# RasPi-BplusHAT.net
KiCad netlist of a schematic drawn in Altium Designer
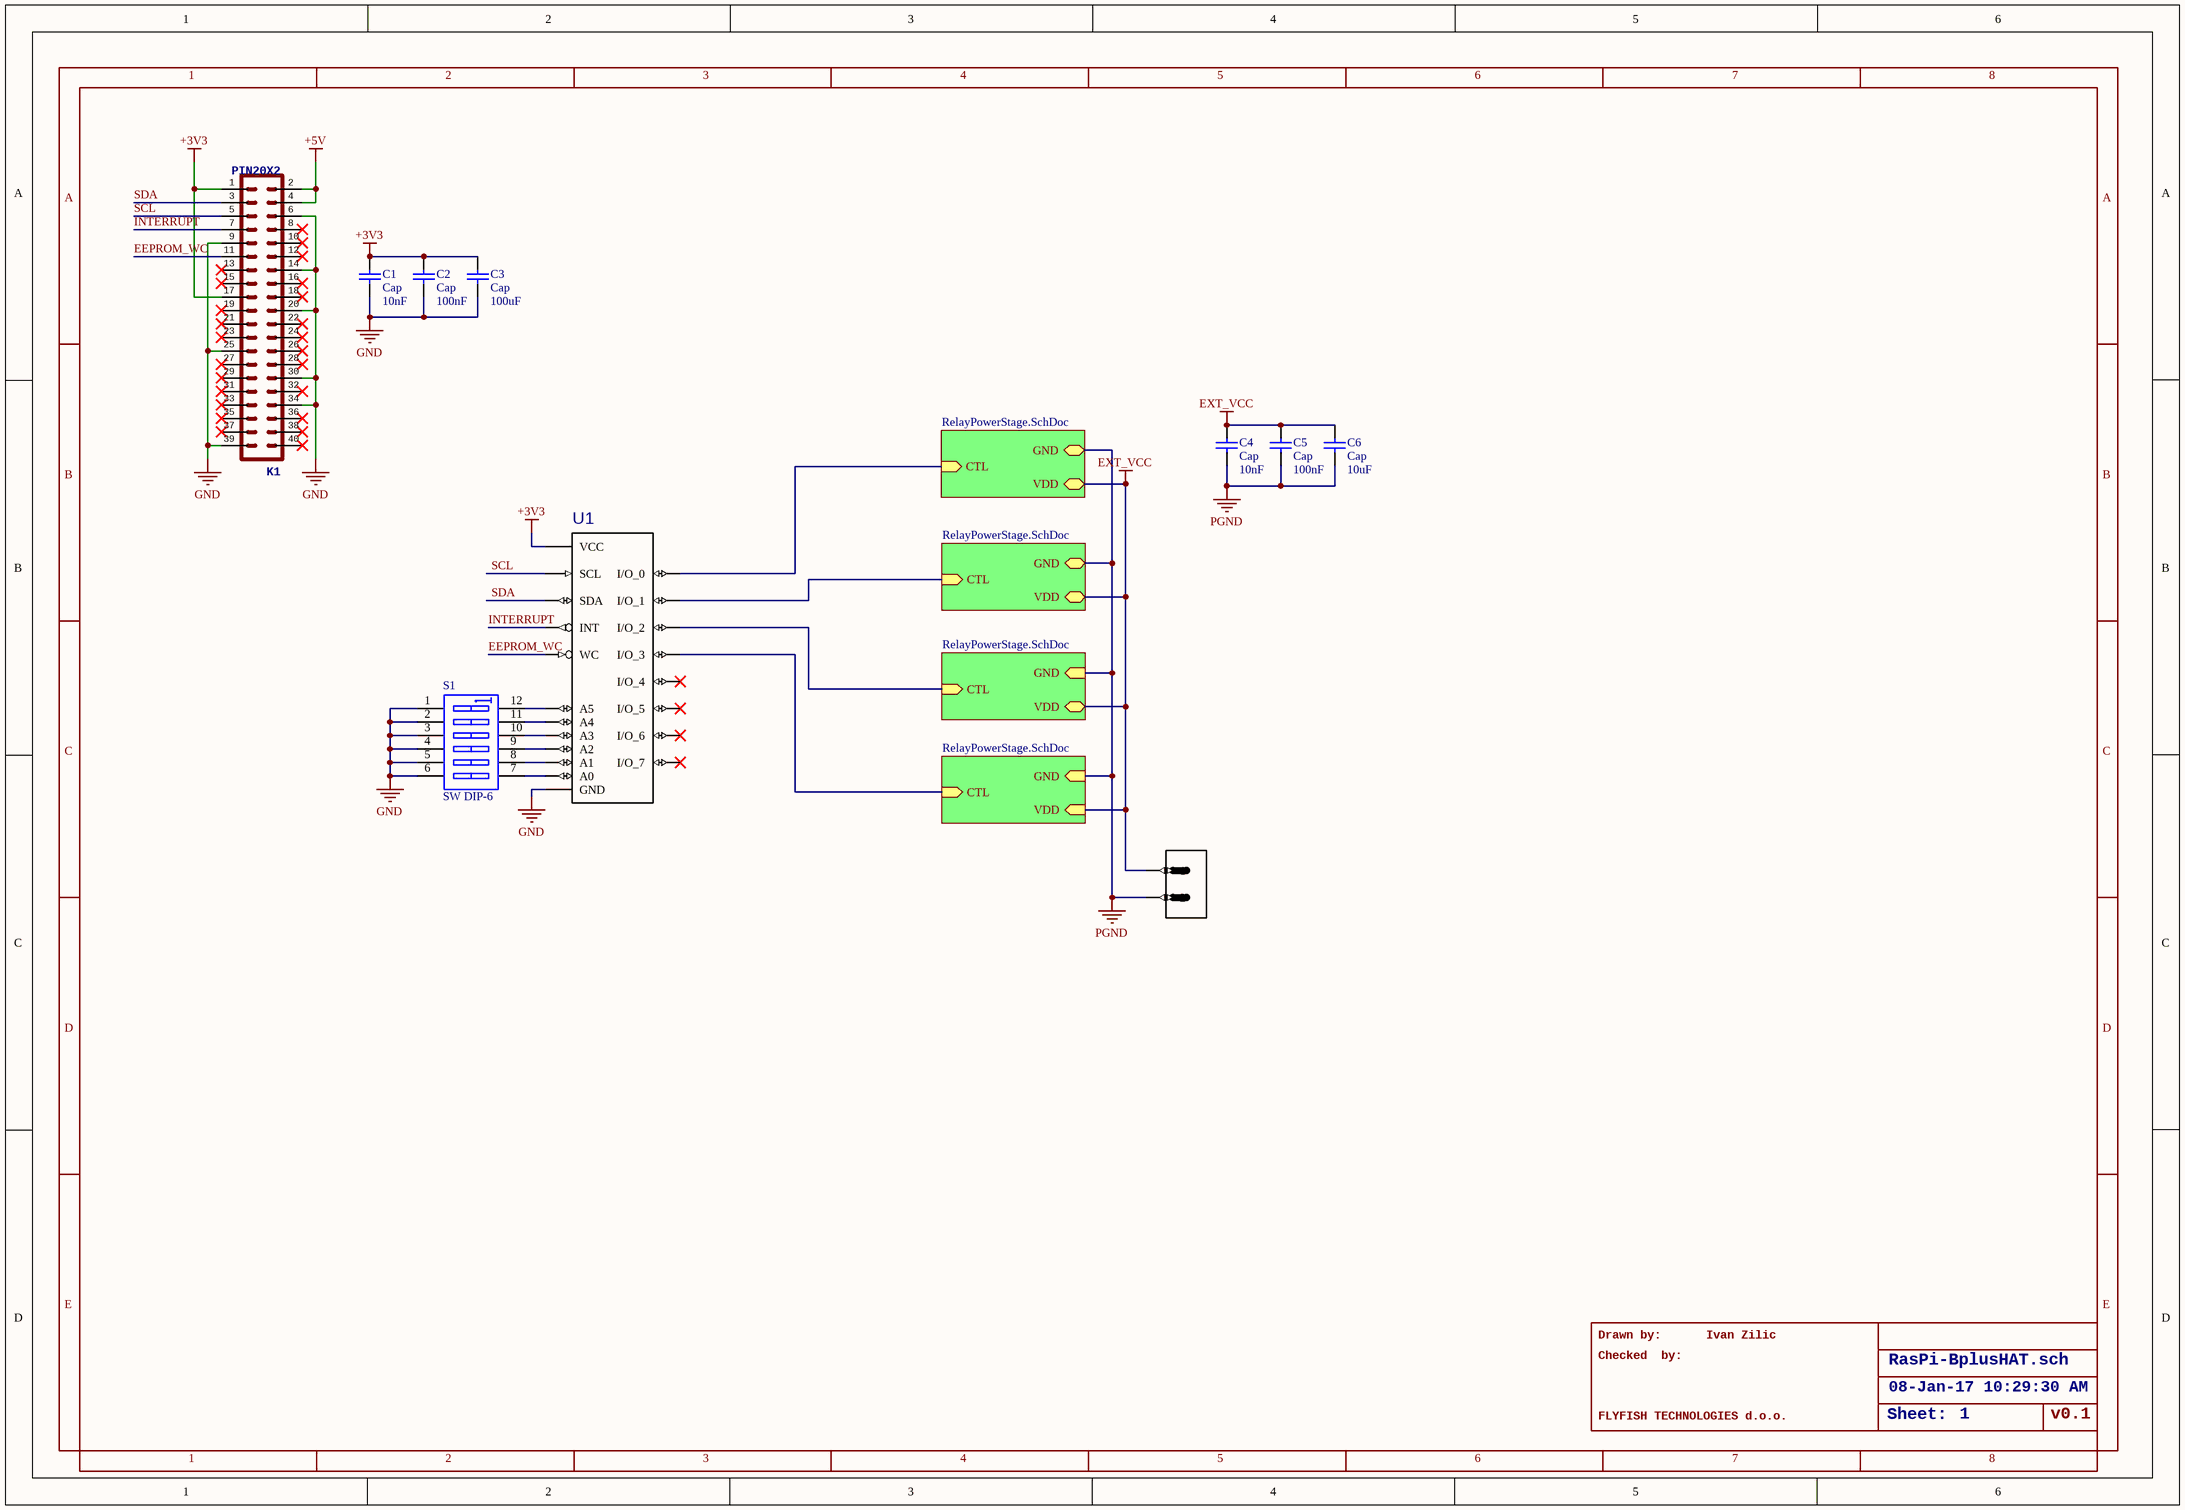
[diagram p0: RasPi-BplusHAT.SchDoc]

(export (version "E")
  (design (tool "Eeschema 10.0.6"))
  (components
    (comp (ref "C1")
      (value "Cap")
      (footprint "6-0805_N")
      (description "Capacitor")
      (fields (field (name "ALTIUM_VALUE") "10nF") (field (name "PUBLISHER") "Altium Limited"))
      (libsource (lib "Miscellaneous Devices") (part "Cap"))
    )
    (comp (ref "C2")
      (value "Cap")
      (footprint "6-0805_N")
      (description "Capacitor")
      (fields (field (name "ALTIUM_VALUE") "100nF") (field (name "PUBLISHER") "Altium Limited"))
      (libsource (lib "Miscellaneous Devices") (part "Cap"))
    )
    (comp (ref "C3")
      (value "Cap")
      (footprint "6-0805_N")
      (description "Capacitor")
      (fields (field (name "ALTIUM_VALUE") "100uF") (field (name "PUBLISHER") "Altium Limited"))
      (libsource (lib "Miscellaneous Devices") (part "Cap"))
    )
    (comp (ref "C4")
      (value "Cap")
      (footprint "6-0805_N")
      (description "Capacitor")
      (fields (field (name "ALTIUM_VALUE") "10nF") (field (name "PUBLISHER") "Altium Limited"))
      (libsource (lib "Miscellaneous Devices") (part "Cap"))
    )
    (comp (ref "C5")
      (value "Cap")
      (footprint "6-0805_N")
      (description "Capacitor")
      (fields (field (name "ALTIUM_VALUE") "100nF") (field (name "PUBLISHER") "Altium Limited"))
      (libsource (lib "Miscellaneous Devices") (part "Cap"))
    )
    (comp (ref "C6")
      (value "Cap")
      (footprint "C1210_N")
      (description "Capacitor")
      (fields (field (name "ALTIUM_VALUE") "10uF") (field (name "PUBLISHER") "Altium Limited"))
      (libsource (lib "Miscellaneous Devices") (part "Cap"))
    )
    (comp (ref "J1")
      (value "1760510000")
      (footprint "1760490000")
      (description "Conn Terminal Block 2 POS 5.08mm Solder ST Thru-Hole 16A")
      (fields (field (name "MF") "Weidmuller"))
      (libsource (lib "1760510000") (part "1760510000"))
    )
    (comp (ref "K1")
      (value "PIN20X2")
      (footprint "HDR2X20")
      (fields (field (name ">VALUE") "PIN20X2") (field (name ">NAME") "K1"))
      (libsource (lib "FLYFISH") (part "PIN20X2"))
    )
    (comp (ref "S1")
      (value "SW DIP-6")
      (footprint "DIP-12/SW")
      (description "DIP Switch, 6 Position, SPST")
      (fields (field (name "PUBLISHER") "Altium Limited"))
      (libsource (lib "Miscellaneous Devices") (part "SW DIP-6"))
    )
    (comp (ref "U1")
      (value "PCA9501")
      (footprint "TSSOP20")
      (fields (field (name "MF") "NXP Semiconductors"))
      (libsource (lib "PCA9501") (part "PCA9501"))
    )
  )
  (nets
    (net (code "1") (name "+3V3") (class "Default")
      (node (ref "C1") (pin "2") (pinfunction "2_2") (pintype "passive"))
      (node (ref "C2") (pin "2") (pinfunction "2_2") (pintype "passive"))
      (node (ref "C3") (pin "2") (pinfunction "2_2") (pintype "passive"))
      (node (ref "K1") (pin "1") (pinfunction "1_1") (pintype "passive"))
      (node (ref "K1") (pin "17") (pinfunction "17_17") (pintype "passive"))
      (node (ref "U1") (pin "20") (pinfunction "VCC_20") (pintype "power_in"))
    )
    (net (code "2") (name "+5V") (class "Default")
      (node (ref "K1") (pin "2") (pinfunction "2_2") (pintype "passive"))
      (node (ref "K1") (pin "4") (pinfunction "4_4") (pintype "passive"))
    )
    (net (code "3") (name "/CTL") (class "Default")
      (node (ref "U1") (pin "7") (pinfunction "I/O_3_7") (pintype "bidirectional"))
    )
    (net (code "4") (name "/CTL_1") (class "Default")
      (node (ref "U1") (pin "4") (pinfunction "I/O_0_4") (pintype "bidirectional"))
    )
    (net (code "5") (name "/CTL_2") (class "Default")
      (node (ref "U1") (pin "5") (pinfunction "I/O_1_5") (pintype "bidirectional"))
    )
    (net (code "6") (name "/CTL_3") (class "Default")
      (node (ref "U1") (pin "6") (pinfunction "I/O_2_6") (pintype "bidirectional"))
    )
    (net (code "7") (name "/EEPROM_WC") (class "Default")
      (node (ref "K1") (pin "11") (pinfunction "11_11") (pintype "passive"))
      (node (ref "U1") (pin "17") (pinfunction "WC_17") (pintype "input"))
    )
    (net (code "8") (name "/INTERRUPT") (class "Default")
      (node (ref "K1") (pin "7") (pinfunction "7_7") (pintype "passive"))
      (node (ref "U1") (pin "8") (pinfunction "INT_8") (pintype "output"))
    )
    (net (code "9") (name "/SCL") (class "Default")
      (node (ref "K1") (pin "5") (pinfunction "5_5") (pintype "passive"))
      (node (ref "U1") (pin "18") (pinfunction "SCL_18") (pintype "input"))
    )
    (net (code "10") (name "/SDA") (class "Default")
      (node (ref "K1") (pin "3") (pinfunction "3_3") (pintype "passive"))
      (node (ref "U1") (pin "19") (pinfunction "SDA_19") (pintype "bidirectional"))
    )
    (net (code "11") (name "EXT_VCC") (class "Default")
      (node (ref "C4") (pin "2") (pinfunction "2_2") (pintype "passive"))
      (node (ref "C5") (pin "2") (pinfunction "2_2") (pintype "passive"))
      (node (ref "C6") (pin "2") (pinfunction "2_2") (pintype "passive"))
      (node (ref "J1") (pin "1") (pinfunction "1_1") (pintype "bidirectional"))
    )
    (net (code "12") (name "GND") (class "Default")
      (node (ref "C1") (pin "1") (pinfunction "1_1") (pintype "passive"))
      (node (ref "C2") (pin "1") (pinfunction "1_1") (pintype "passive"))
      (node (ref "C3") (pin "1") (pinfunction "1_1") (pintype "passive"))
      (node (ref "K1") (pin "14") (pinfunction "14_14") (pintype "passive"))
      (node (ref "K1") (pin "20") (pinfunction "20_20") (pintype "passive"))
      (node (ref "K1") (pin "25") (pinfunction "25_25") (pintype "passive"))
      (node (ref "K1") (pin "30") (pinfunction "30_30") (pintype "passive"))
      (node (ref "K1") (pin "34") (pinfunction "34_34") (pintype "passive"))
      (node (ref "K1") (pin "39") (pinfunction "39_39") (pintype "passive"))
      (node (ref "K1") (pin "6") (pinfunction "6_6") (pintype "passive"))
      (node (ref "K1") (pin "9") (pinfunction "9_9") (pintype "passive"))
      (node (ref "S1") (pin "1") (pinfunction "A1_1") (pintype "passive"))
      (node (ref "S1") (pin "2") (pinfunction "A2_2") (pintype "passive"))
      (node (ref "S1") (pin "3") (pinfunction "A3_3") (pintype "passive"))
      (node (ref "S1") (pin "4") (pinfunction "A4_4") (pintype "passive"))
      (node (ref "S1") (pin "5") (pinfunction "A5_5") (pintype "passive"))
      (node (ref "S1") (pin "6") (pinfunction "A6_6") (pintype "passive"))
      (node (ref "U1") (pin "10") (pinfunction "GND_10") (pintype "power_in"))
    )
    (net (code "13") (name "Net-(S1-B1)") (class "Default")
      (node (ref "S1") (pin "12") (pinfunction "B1_12") (pintype "passive"))
      (node (ref "U1") (pin "9") (pinfunction "A5_9") (pintype "bidirectional"))
    )
    (net (code "14") (name "Net-(S1-B2)") (class "Default")
      (node (ref "S1") (pin "11") (pinfunction "B2_11") (pintype "passive"))
      (node (ref "U1") (pin "11") (pinfunction "A4_11") (pintype "bidirectional"))
    )
    (net (code "15") (name "Net-(S1-B3)") (class "Default")
      (node (ref "S1") (pin "10") (pinfunction "B3_10") (pintype "passive"))
      (node (ref "U1") (pin "12") (pinfunction "A3_12") (pintype "bidirectional"))
    )
    (net (code "16") (name "Net-(S1-B4)") (class "Default")
      (node (ref "S1") (pin "9") (pinfunction "B4_9") (pintype "passive"))
      (node (ref "U1") (pin "3") (pinfunction "A2_3") (pintype "bidirectional"))
    )
    (net (code "17") (name "Net-(S1-B5)") (class "Default")
      (node (ref "S1") (pin "8") (pinfunction "B5_8") (pintype "passive"))
      (node (ref "U1") (pin "2") (pinfunction "A1_2") (pintype "bidirectional"))
    )
    (net (code "18") (name "Net-(S1-B6)") (class "Default")
      (node (ref "S1") (pin "7") (pinfunction "B6_7") (pintype "passive"))
      (node (ref "U1") (pin "1") (pinfunction "A0_1") (pintype "bidirectional"))
    )
    (net (code "19") (name "PGND") (class "Default")
      (node (ref "C4") (pin "1") (pinfunction "1_1") (pintype "passive"))
      (node (ref "C5") (pin "1") (pinfunction "1_1") (pintype "passive"))
      (node (ref "C6") (pin "1") (pinfunction "1_1") (pintype "passive"))
      (node (ref "J1") (pin "2") (pinfunction "2_2") (pintype "bidirectional"))
    )
    (net (code "20") (name "unconnected-(K1-Pad8)") (class "Default")
      (node (ref "K1") (pin "8") (pinfunction "8_8") (pintype "passive+no_connect"))
    )
    (net (code "21") (name "unconnected-(K1-Pad10)") (class "Default")
      (node (ref "K1") (pin "10") (pinfunction "10_10") (pintype "passive+no_connect"))
    )
    (net (code "22") (name "unconnected-(K1-Pad12)") (class "Default")
      (node (ref "K1") (pin "12") (pinfunction "12_12") (pintype "passive+no_connect"))
    )
    (net (code "23") (name "unconnected-(K1-Pad13)") (class "Default")
      (node (ref "K1") (pin "13") (pinfunction "13_13") (pintype "passive+no_connect"))
    )
    (net (code "24") (name "unconnected-(K1-Pad15)") (class "Default")
      (node (ref "K1") (pin "15") (pinfunction "15_15") (pintype "passive+no_connect"))
    )
    (net (code "25") (name "unconnected-(K1-Pad16)") (class "Default")
      (node (ref "K1") (pin "16") (pinfunction "16_16") (pintype "passive+no_connect"))
    )
    (net (code "26") (name "unconnected-(K1-Pad18)") (class "Default")
      (node (ref "K1") (pin "18") (pinfunction "18_18") (pintype "passive+no_connect"))
    )
    (net (code "27") (name "unconnected-(K1-Pad19)") (class "Default")
      (node (ref "K1") (pin "19") (pinfunction "19_19") (pintype "passive+no_connect"))
    )
    (net (code "28") (name "unconnected-(K1-Pad21)") (class "Default")
      (node (ref "K1") (pin "21") (pinfunction "21_21") (pintype "passive+no_connect"))
    )
    (net (code "29") (name "unconnected-(K1-Pad22)") (class "Default")
      (node (ref "K1") (pin "22") (pinfunction "22_22") (pintype "passive+no_connect"))
    )
    (net (code "30") (name "unconnected-(K1-Pad23)") (class "Default")
      (node (ref "K1") (pin "23") (pinfunction "23_23") (pintype "passive+no_connect"))
    )
    (net (code "31") (name "unconnected-(K1-Pad24)") (class "Default")
      (node (ref "K1") (pin "24") (pinfunction "24_24") (pintype "passive+no_connect"))
    )
    (net (code "32") (name "unconnected-(K1-Pad26)") (class "Default")
      (node (ref "K1") (pin "26") (pinfunction "26_26") (pintype "passive+no_connect"))
    )
    (net (code "33") (name "unconnected-(K1-Pad27)") (class "Default")
      (node (ref "K1") (pin "27") (pinfunction "27_27") (pintype "passive+no_connect"))
    )
    (net (code "34") (name "unconnected-(K1-Pad28)") (class "Default")
      (node (ref "K1") (pin "28") (pinfunction "28_28") (pintype "passive+no_connect"))
    )
    (net (code "35") (name "unconnected-(K1-Pad29)") (class "Default")
      (node (ref "K1") (pin "29") (pinfunction "29_29") (pintype "passive+no_connect"))
    )
    (net (code "36") (name "unconnected-(K1-Pad31)") (class "Default")
      (node (ref "K1") (pin "31") (pinfunction "31_31") (pintype "passive+no_connect"))
    )
    (net (code "37") (name "unconnected-(K1-Pad32)") (class "Default")
      (node (ref "K1") (pin "32") (pinfunction "32_32") (pintype "passive+no_connect"))
    )
    (net (code "38") (name "unconnected-(K1-Pad33)") (class "Default")
      (node (ref "K1") (pin "33") (pinfunction "33_33") (pintype "passive+no_connect"))
    )
    (net (code "39") (name "unconnected-(K1-Pad35)") (class "Default")
      (node (ref "K1") (pin "35") (pinfunction "35_35") (pintype "passive+no_connect"))
    )
    (net (code "40") (name "unconnected-(K1-Pad36)") (class "Default")
      (node (ref "K1") (pin "36") (pinfunction "36_36") (pintype "passive+no_connect"))
    )
    (net (code "41") (name "unconnected-(K1-Pad37)") (class "Default")
      (node (ref "K1") (pin "37") (pinfunction "37_37") (pintype "passive+no_connect"))
    )
    (net (code "42") (name "unconnected-(K1-Pad38)") (class "Default")
      (node (ref "K1") (pin "38") (pinfunction "38_38") (pintype "passive+no_connect"))
    )
    (net (code "43") (name "unconnected-(K1-Pad40)") (class "Default")
      (node (ref "K1") (pin "40") (pinfunction "40_40") (pintype "passive+no_connect"))
    )
    (net (code "44") (name "unconnected-(U1-I{slash}O_4-Pad13)") (class "Default")
      (node (ref "U1") (pin "13") (pinfunction "I/O_4_13") (pintype "bidirectional+no_connect"))
    )
    (net (code "45") (name "unconnected-(U1-I{slash}O_5-Pad14)") (class "Default")
      (node (ref "U1") (pin "14") (pinfunction "I/O_5_14") (pintype "bidirectional+no_connect"))
    )
    (net (code "46") (name "unconnected-(U1-I{slash}O_6-Pad15)") (class "Default")
      (node (ref "U1") (pin "15") (pinfunction "I/O_6_15") (pintype "bidirectional+no_connect"))
    )
    (net (code "47") (name "unconnected-(U1-I{slash}O_7-Pad16)") (class "Default")
      (node (ref "U1") (pin "16") (pinfunction "I/O_7_16") (pintype "bidirectional+no_connect"))
    )
  )
)
